# Fri3D_2020_01.net
KiCad netlist of a schematic drawn in Altium Designer
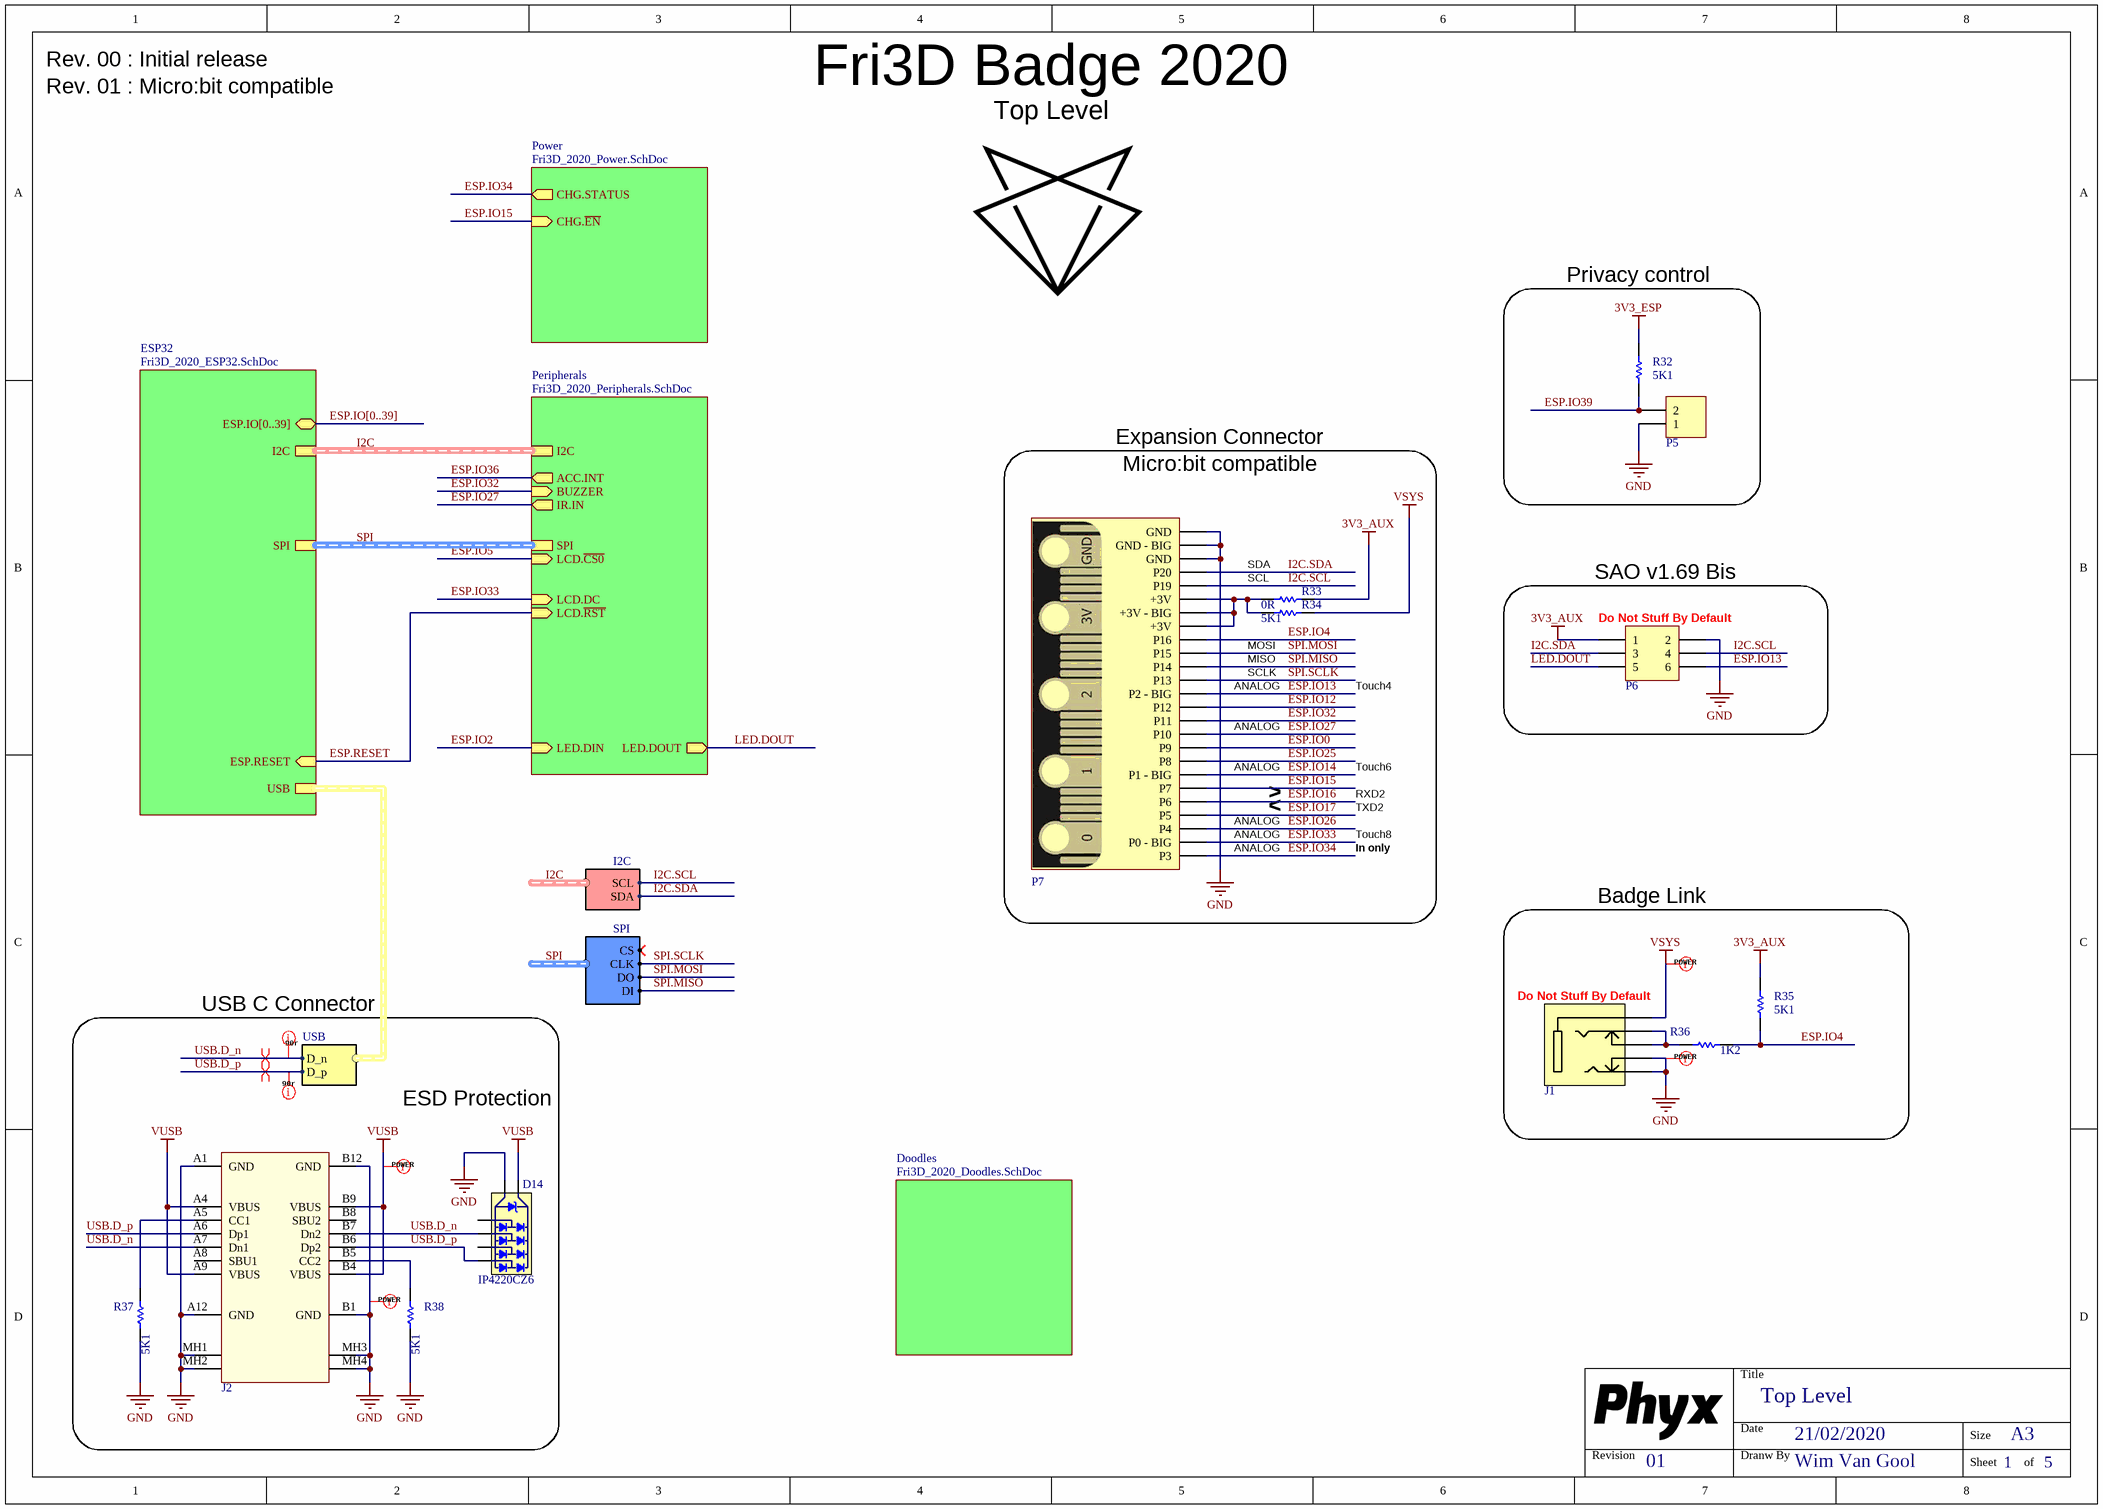
[diagram p0: Fri3D_2020_01.SchDoc]

(export (version "E")
  (design (tool "Eeschema 10.0.6"))
  (components
    (comp (ref "D14")
      (value "IP4220CZ6")
      (footprint "NXP_SOT457")
      (description "=Description")
      (fields (field (name "Comment") "TVS Diode Dual USB"))
      (libsource (lib "Phyx_Components") (part "NXP_IP4220CZ6"))
    )
    (comp (ref "J1")
      (value "3.5mm jack, dual switch, black, 3 contacts")
      (footprint "CUI_SJ1-3525NG")
      (description "=Description")
      (libsource (lib "Phyx_Components") (part "CUI_SJ1-3525NG"))
    )
    (comp (ref "J2")
      (value "USB 2.0 C Reversible Receptacle Horizontal")
      (footprint "HRO_TYPE-C-31-M-12")
      (libsource (lib "Phyx_Components") (part "USB_C_16_4"))
    )
    (comp (ref "P5")
      (value "Easy to solder connection")
      (footprint "SOLDER_SW_V_1MM")
      (libsource (lib "Phyx_Components") (part "Header 2"))
    )
    (comp (ref "P6")
      (value "Receptacle 3x2")
      (footprint "RCPT2X3")
      (libsource (lib "Phyx_Components") (part "Header 3X2"))
    )
    (comp (ref "P7")
      (value "MicroBit PCB connector")
      (footprint "MicroBIT_PCB")
      (libsource (lib "Phyx_Components") (part "Header 25_MicroBit"))
    )
    (comp (ref "R32")
      (value "5K1")
      (footprint "R0603_N")
      (fields (field (name "Comment") "RESISTOR"))
      (libsource (lib "Phyx_Components") (part "RESISTOR"))
    )
    (comp (ref "R33")
      (value "0R")
      (footprint "R0603_N")
      (fields (field (name "Comment") "RESISTOR"))
      (libsource (lib "Phyx_Components") (part "RESISTOR"))
    )
    (comp (ref "R34")
      (value "5K1")
      (footprint "R0603_N")
      (fields (field (name "Comment") "RESISTOR"))
      (libsource (lib "Phyx_Components") (part "RESISTOR"))
    )
    (comp (ref "R35")
      (value "5K1")
      (footprint "R0603_N")
      (fields (field (name "Comment") "RESISTOR"))
      (libsource (lib "Phyx_Components") (part "RESISTOR"))
    )
    (comp (ref "R36")
      (value "1K2")
      (footprint "R0603_N")
      (fields (field (name "Comment") "RESISTOR"))
      (libsource (lib "Phyx_Components") (part "RESISTOR"))
    )
    (comp (ref "R37")
      (value "5K1")
      (footprint "R0603_N")
      (fields (field (name "Comment") "RESISTOR"))
      (libsource (lib "Phyx_Components") (part "RESISTOR"))
    )
    (comp (ref "R38")
      (value "5K1")
      (footprint "R0603_N")
      (fields (field (name "Comment") "RESISTOR"))
      (libsource (lib "Phyx_Components") (part "RESISTOR"))
    )
  )
  (nets
    (net (code "28") (name "/ESP.IO0") (class "Default")
      (node (ref "P7") (pin "9") (pinfunction "P9_9") (pintype "passive"))
    )
    (net (code "30") (name "/ESP.IO4") (class "Default")
      (node (ref "P7") (pin "17") (pinfunction "P16_17") (pintype "passive"))
      (node (ref "R35") (pin "2") (pinfunction "2_2") (pintype "passive"))
      (node (ref "R36") (pin "1") (pinfunction "1_1") (pintype "passive"))
    )
    (net (code "32") (name "/ESP.IO12") (class "Default")
      (node (ref "P7") (pin "12") (pinfunction "P12_12") (pintype "passive"))
    )
    (net (code "33") (name "/ESP.IO13") (class "Default")
      (node (ref "P6") (pin "6") (pinfunction "6_6") (pintype "passive"))
      (node (ref "P7") (pin "13") (pinfunction "P2_-_BIG_13") (pintype "passive"))
    )
    (net (code "34") (name "/ESP.IO14") (class "Default")
      (node (ref "P7") (pin "7") (pinfunction "P1_-_BIG_7") (pintype "passive"))
    )
    (net (code "35") (name "/ESP.IO15") (class "Default")
      (node (ref "P7") (pin "6") (pinfunction "P7_6") (pintype "passive"))
    )
    (net (code "36") (name "/ESP.IO16") (class "Default")
      (node (ref "P7") (pin "5") (pinfunction "P6_5") (pintype "passive"))
    )
    (net (code "37") (name "/ESP.IO17") (class "Default")
      (node (ref "P7") (pin "4") (pinfunction "P5_4") (pintype "passive"))
    )
    (net (code "38") (name "/ESP.IO25") (class "Default")
      (node (ref "P7") (pin "8") (pinfunction "P8_8") (pintype "passive"))
    )
    (net (code "39") (name "/ESP.IO26") (class "Default")
      (node (ref "P7") (pin "3") (pinfunction "P4_3") (pintype "passive"))
    )
    (net (code "40") (name "/ESP.IO27") (class "Default")
      (node (ref "P7") (pin "10") (pinfunction "P10_10") (pintype "passive"))
    )
    (net (code "41") (name "/ESP.IO32") (class "Default")
      (node (ref "P7") (pin "11") (pinfunction "P11_11") (pintype "passive"))
    )
    (net (code "42") (name "/ESP.IO33") (class "Default")
      (node (ref "P7") (pin "2") (pinfunction "P0_-_BIG_2") (pintype "passive"))
    )
    (net (code "43") (name "/ESP.IO34") (class "Default")
      (node (ref "P7") (pin "1") (pinfunction "P3_1") (pintype "passive"))
    )
    (net (code "45") (name "/ESP.IO39") (class "Default")
      (node (ref "P5") (pin "2") (pinfunction "2_2") (pintype "passive"))
      (node (ref "R32") (pin "2") (pinfunction "2_2") (pintype "passive"))
    )
    (net (code "48") (name "/I2C.SCL") (class "Default")
      (node (ref "P6") (pin "4") (pinfunction "4_4") (pintype "passive"))
      (node (ref "P7") (pin "21") (pinfunction "P19_21") (pintype "passive"))
    )
    (net (code "49") (name "/I2C.SDA") (class "Default")
      (node (ref "P6") (pin "3") (pinfunction "3_3") (pintype "passive"))
      (node (ref "P7") (pin "22") (pinfunction "P20_22") (pintype "passive"))
    )
    (net (code "51") (name "/LED.DOUT") (class "Default")
      (node (ref "P6") (pin "5") (pinfunction "5_5") (pintype "passive"))
    )
    (net (code "52") (name "/SPI.MISO") (class "Default")
      (node (ref "P7") (pin "15") (pinfunction "P14_15") (pintype "passive"))
    )
    (net (code "53") (name "/SPI.MOSI") (class "Default")
      (node (ref "P7") (pin "16") (pinfunction "P15_16") (pintype "passive"))
    )
    (net (code "54") (name "/SPI.SCLK") (class "Default")
      (node (ref "P7") (pin "14") (pinfunction "P13_14") (pintype "passive"))
    )
    (net (code "56") (name "/USB.D_n") (class "Default")
      (node (ref "D14") (pin "1") (pinfunction "1_1") (pintype "passive"))
      (node (ref "J2") (pin "A7") (pinfunction "Dn1_A7") (pintype "passive"))
      (node (ref "J2") (pin "B7") (pinfunction "Dn2_B7") (pintype "passive"))
    )
    (net (code "57") (name "/USB.D_p") (class "Default")
      (node (ref "D14") (pin "6") (pinfunction "6_6") (pintype "passive"))
      (node (ref "J2") (pin "A6") (pinfunction "Dp1_A6") (pintype "passive"))
      (node (ref "J2") (pin "B6") (pinfunction "Dp2_B6") (pintype "passive"))
    )
    (net (code "61") (name "3V3_AUX") (class "Default")
      (node (ref "P6") (pin "1") (pinfunction "1_1") (pintype "passive"))
      (node (ref "R33") (pin "1") (pinfunction "1_1") (pintype "passive"))
      (node (ref "R35") (pin "1") (pinfunction "1_1") (pintype "passive"))
    )
    (net (code "62") (name "3V3_ESP") (class "Default")
      (node (ref "R32") (pin "1") (pinfunction "1_1") (pintype "passive"))
    )
    (net (code "63") (name "GND") (class "Default")
      (node (ref "D14") (pin "2") (pinfunction "GND_2") (pintype "passive"))
      (node (ref "J1") (pin "2") (pinfunction "Tip_2") (pintype "passive"))
      (node (ref "J1") (pin "4") (pinfunction "4_4") (pintype "passive"))
      (node (ref "J2") (pin "A1") (pinfunction "GND_A1") (pintype "passive"))
      (node (ref "J2") (pin "A12") (pinfunction "GND_A12") (pintype "passive"))
      (node (ref "J2") (pin "B1") (pinfunction "GND_B1") (pintype "passive"))
      (node (ref "J2") (pin "B12") (pinfunction "GND_B12") (pintype "passive"))
      (node (ref "J2") (pin "MH1") (pinfunction "Tab_MH1") (pintype "passive"))
      (node (ref "J2") (pin "MH2") (pinfunction "Tab_MH2") (pintype "passive"))
      (node (ref "J2") (pin "MH3") (pinfunction "Tab_MH3") (pintype "passive"))
      (node (ref "J2") (pin "MH4") (pinfunction "Tab_MH4") (pintype "passive"))
      (node (ref "P5") (pin "1") (pinfunction "1_1") (pintype "passive"))
      (node (ref "P6") (pin "2") (pinfunction "2_2") (pintype "passive"))
      (node (ref "P7") (pin "23") (pinfunction "GND_23") (pintype "passive"))
      (node (ref "P7") (pin "24") (pinfunction "GND_-_BIG_24") (pintype "passive"))
      (node (ref "P7") (pin "25") (pinfunction "GND_25") (pintype "passive"))
      (node (ref "R37") (pin "2") (pinfunction "2_2") (pintype "passive"))
      (node (ref "R38") (pin "2") (pinfunction "2_2") (pintype "passive"))
    )
    (net (code "64") (name "Net-(J1-Ring)") (class "Default")
      (node (ref "J1") (pin "3") (pinfunction "Ring_3") (pintype "passive"))
      (node (ref "J1") (pin "5") (pinfunction "5_5") (pintype "passive"))
      (node (ref "R36") (pin "2") (pinfunction "2_2") (pintype "passive"))
    )
    (net (code "65") (name "Net-(J2-CC1)") (class "Default")
      (node (ref "J2") (pin "A5") (pinfunction "CC1_A5") (pintype "passive"))
      (node (ref "R37") (pin "1") (pinfunction "1_1") (pintype "passive"))
    )
    (net (code "66") (name "Net-(J2-CC2)") (class "Default")
      (node (ref "J2") (pin "B5") (pinfunction "CC2_B5") (pintype "passive"))
      (node (ref "R38") (pin "1") (pinfunction "1_1") (pintype "passive"))
    )
    (net (code "67") (name "Net-(P7-+3V_-_BIG)") (class "Default")
      (node (ref "P7") (pin "18") (pinfunction "+3V_18") (pintype "passive"))
      (node (ref "P7") (pin "19") (pinfunction "+3V_-_BIG_19") (pintype "passive"))
      (node (ref "P7") (pin "20") (pinfunction "+3V_20") (pintype "passive"))
      (node (ref "R33") (pin "2") (pinfunction "2_2") (pintype "passive"))
      (node (ref "R34") (pin "1") (pinfunction "1_1") (pintype "passive"))
    )
    (net (code "68") (name "VSYS") (class "Default")
      (node (ref "J1") (pin "1") (pinfunction "Sleeve_1") (pintype "passive"))
      (node (ref "R34") (pin "2") (pinfunction "2_2") (pintype "passive"))
    )
    (net (code "69") (name "VUSB") (class "Default")
      (node (ref "D14") (pin "5") (pinfunction "VBus_5") (pintype "passive"))
      (node (ref "J2") (pin "A4") (pinfunction "VBUS_A4") (pintype "passive"))
      (node (ref "J2") (pin "A9") (pinfunction "VBUS_A9") (pintype "passive"))
      (node (ref "J2") (pin "B4") (pinfunction "VBUS_B4") (pintype "passive"))
      (node (ref "J2") (pin "B9") (pinfunction "VBUS_B9") (pintype "passive"))
    )
    (net (code "70") (name "unconnected-(D14-Pad3)") (class "Default")
      (node (ref "D14") (pin "3") (pinfunction "3_3") (pintype "passive"))
    )
    (net (code "71") (name "unconnected-(D14-Pad4)") (class "Default")
      (node (ref "D14") (pin "4") (pinfunction "4_4") (pintype "passive"))
    )
    (net (code "72") (name "unconnected-(J2-SBU1-PadA8)") (class "Default")
      (node (ref "J2") (pin "A8") (pinfunction "SBU1_A8") (pintype "passive"))
    )
    (net (code "73") (name "unconnected-(J2-SBU2-PadB8)") (class "Default")
      (node (ref "J2") (pin "B8") (pinfunction "SBU2_B8") (pintype "passive"))
    )
  )
)
